# ccu_board.net
KiCad netlist of a schematic drawn in EAGLE
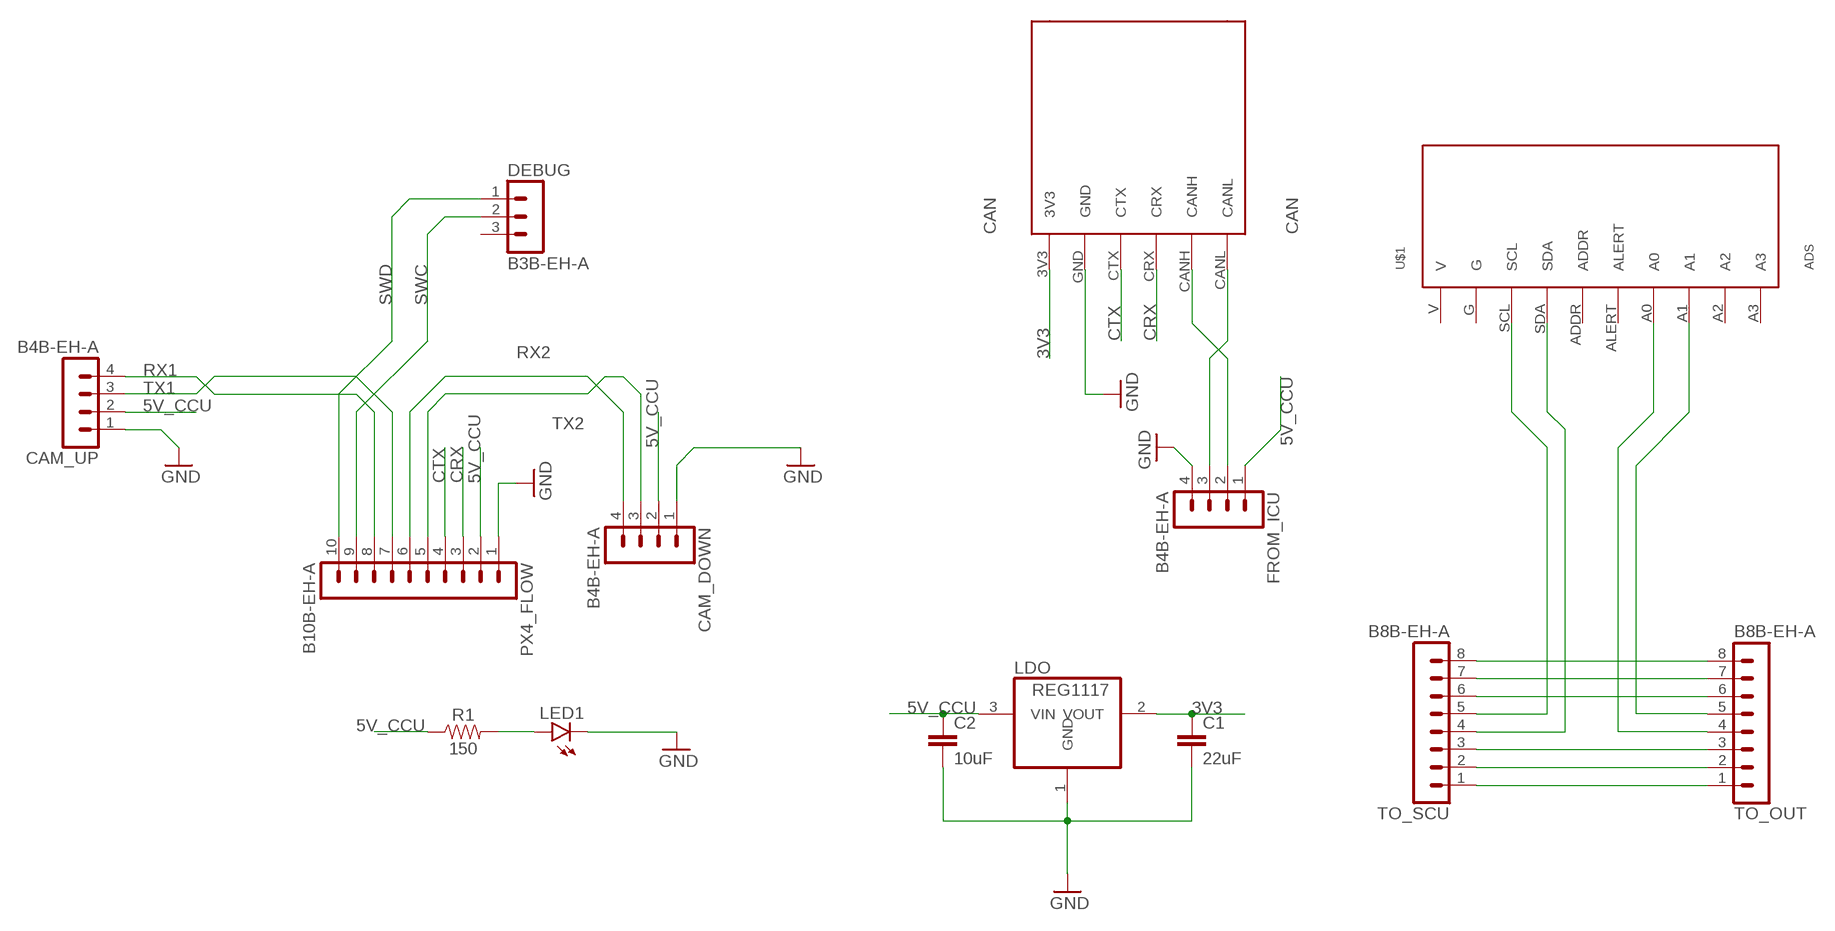
[diagram p0: schematic, sheet 1]

(export (version "E")
  (design (tool "Eeschema 10.0.6"))
  (components
    (comp (ref "C1")
      (value "22uF")
      (footprint "eagle-import:0805")
      (libsource (lib "eagle-import") (part "22UF-0805-6.3V-20%"))
    )
    (comp (ref "C2")
      (value "10uF")
      (footprint "eagle-import:0805")
      (libsource (lib "eagle-import") (part "22UF-0805-16V-20%"))
    )
    (comp (ref "CAM_DOWN")
      (value "B4B-EH-A")
      (footprint "eagle-import:B4B-EH-A")
      (libsource (lib "eagle-import") (part "B4B-EH-A"))
    )
    (comp (ref "CAM_UP")
      (value "B4B-EH-A")
      (footprint "eagle-import:B4B-EH-A")
      (libsource (lib "eagle-import") (part "B4B-EH-A"))
    )
    (comp (ref "CAN")
      (value "CAN")
      (footprint "eagle-import:CAN")
      (libsource (lib "eagle-import") (part "CAN"))
    )
    (comp (ref "DEBUG")
      (value "B3B-EH-A")
      (footprint "eagle-import:B3B-EH-A")
      (libsource (lib "eagle-import") (part "B3B-EH-A"))
    )
    (comp (ref "FROM_ICU")
      (value "B4B-EH-A")
      (footprint "eagle-import:B4B-EH-A")
      (libsource (lib "eagle-import") (part "B4B-EH-A"))
    )
    (comp (ref "LDO")
      (value "REG1117")
      (footprint "eagle-import:SOT223")
      (libsource (lib "eagle-import") (part "REG1117"))
    )
    (comp (ref "LED1")
      (value "LED5MM")
      (footprint "eagle-import:LED5MM")
      (libsource (lib "eagle-import") (part "LED5MM"))
    )
    (comp (ref "PX4_FLOW")
      (value "B10B-EH-A")
      (footprint "eagle-import:B10B-EH-A")
      (libsource (lib "eagle-import") (part "B10B-EH-A"))
    )
    (comp (ref "R1")
      (value "150")
      (footprint "eagle-import:AXIAL-0.3")
      (libsource (lib "eagle-import") (part "RESISTORAXIAL-0.3"))
    )
    (comp (ref "TO_OUT")
      (value "B8B-EH-A")
      (footprint "eagle-import:B8B-EH-A")
      (libsource (lib "eagle-import") (part "B8B-EH-A"))
    )
    (comp (ref "TO_SCU")
      (value "B8B-EH-A")
      (footprint "eagle-import:B8B-EH-A")
      (libsource (lib "eagle-import") (part "B8B-EH-A"))
    )
    (comp (ref "U$1")
      (value "ADS")
      (footprint "eagle-import:ADS")
      (libsource (lib "eagle-import") (part "ADS"))
    )
  )
  (nets
    (net (code "1") (name "/3V3") (class "Default")
      (node (ref "C1") (pin "1") (pinfunction "1_1") (pintype "passive"))
      (node (ref "CAN") (pin "3V3") (pinfunction "3V3_3V3") (pintype "bidirectional"))
      (node (ref "LDO") (pin "2") (pinfunction "VOUT_2") (pintype "output"))
    )
    (net (code "2") (name "/5V_CCU") (class "Default")
      (node (ref "C2") (pin "1") (pinfunction "1_1") (pintype "passive"))
      (node (ref "CAM_DOWN") (pin "2") (pinfunction "2_2") (pintype "passive"))
      (node (ref "CAM_UP") (pin "2") (pinfunction "2_2") (pintype "passive"))
      (node (ref "FROM_ICU") (pin "1") (pinfunction "1_1") (pintype "passive"))
      (node (ref "LDO") (pin "3") (pinfunction "VIN_3") (pintype "input"))
      (node (ref "PX4_FLOW") (pin "2") (pinfunction "2_2") (pintype "passive"))
      (node (ref "R1") (pin "P$1") (pinfunction "1_P$1") (pintype "passive"))
    )
    (net (code "3") (name "/CRX") (class "Default")
      (node (ref "CAN") (pin "CRX") (pinfunction "CRX_CRX") (pintype "bidirectional"))
      (node (ref "PX4_FLOW") (pin "3") (pinfunction "3_3") (pintype "passive"))
    )
    (net (code "4") (name "/CTX") (class "Default")
      (node (ref "CAN") (pin "CTX") (pinfunction "CTX_CTX") (pintype "bidirectional"))
      (node (ref "PX4_FLOW") (pin "4") (pinfunction "4_4") (pintype "passive"))
    )
    (net (code "5") (name "/RX1") (class "Default")
      (node (ref "CAM_UP") (pin "4") (pinfunction "4_4") (pintype "passive"))
      (node (ref "PX4_FLOW") (pin "8") (pinfunction "8_8") (pintype "passive"))
    )
    (net (code "6") (name "/RX2") (class "Default")
      (node (ref "CAM_DOWN") (pin "4") (pinfunction "4_4") (pintype "passive"))
      (node (ref "PX4_FLOW") (pin "6") (pinfunction "6_6") (pintype "passive"))
    )
    (net (code "7") (name "/SWC") (class "Default")
      (node (ref "DEBUG") (pin "2") (pinfunction "2_2") (pintype "passive"))
      (node (ref "PX4_FLOW") (pin "9") (pinfunction "9_9") (pintype "passive"))
    )
    (net (code "8") (name "/SWD") (class "Default")
      (node (ref "DEBUG") (pin "1") (pinfunction "1_1") (pintype "passive"))
      (node (ref "PX4_FLOW") (pin "10") (pinfunction "10_10") (pintype "passive"))
    )
    (net (code "9") (name "/TX1") (class "Default")
      (node (ref "CAM_UP") (pin "3") (pinfunction "3_3") (pintype "passive"))
      (node (ref "PX4_FLOW") (pin "7") (pinfunction "7_7") (pintype "passive"))
    )
    (net (code "10") (name "/TX2") (class "Default")
      (node (ref "CAM_DOWN") (pin "3") (pinfunction "3_3") (pintype "passive"))
      (node (ref "PX4_FLOW") (pin "5") (pinfunction "5_5") (pintype "passive"))
    )
    (net (code "11") (name "GND") (class "Default")
      (node (ref "C1") (pin "2") (pinfunction "2_2") (pintype "passive"))
      (node (ref "C2") (pin "2") (pinfunction "2_2") (pintype "passive"))
      (node (ref "CAM_DOWN") (pin "1") (pinfunction "1_1") (pintype "passive"))
      (node (ref "CAM_UP") (pin "1") (pinfunction "1_1") (pintype "passive"))
      (node (ref "CAN") (pin "GND") (pinfunction "GND_GND") (pintype "bidirectional"))
      (node (ref "FROM_ICU") (pin "4") (pinfunction "4_4") (pintype "passive"))
      (node (ref "LDO") (pin "1") (pinfunction "GND_1") (pintype "power_in"))
      (node (ref "LED1") (pin "K") (pinfunction "C_K") (pintype "passive"))
      (node (ref "PX4_FLOW") (pin "1") (pinfunction "1_1") (pintype "passive"))
    )
    (net (code "12") (name "Net-(CAN-PadCANH)") (class "Default")
      (node (ref "CAN") (pin "CANH") (pinfunction "CANH_CANH") (pintype "bidirectional"))
      (node (ref "FROM_ICU") (pin "2") (pinfunction "2_2") (pintype "passive"))
    )
    (net (code "13") (name "Net-(CAN-PadCANL)") (class "Default")
      (node (ref "CAN") (pin "CANL") (pinfunction "CANL_CANL") (pintype "bidirectional"))
      (node (ref "FROM_ICU") (pin "3") (pinfunction "3_3") (pintype "passive"))
    )
    (net (code "14") (name "Net-(R1-2)") (class "Default")
      (node (ref "LED1") (pin "A") (pinfunction "A_A") (pintype "passive"))
      (node (ref "R1") (pin "P$2") (pinfunction "2_P$2") (pintype "passive"))
    )
    (net (code "15") (name "Net-(TO_OUT-Pad1)") (class "Default")
      (node (ref "TO_OUT") (pin "1") (pinfunction "1_1") (pintype "passive"))
      (node (ref "TO_SCU") (pin "1") (pinfunction "1_1") (pintype "passive"))
    )
    (net (code "16") (name "Net-(TO_OUT-Pad2)") (class "Default")
      (node (ref "TO_OUT") (pin "2") (pinfunction "2_2") (pintype "passive"))
      (node (ref "TO_SCU") (pin "2") (pinfunction "2_2") (pintype "passive"))
    )
    (net (code "17") (name "Net-(TO_OUT-Pad3)") (class "Default")
      (node (ref "TO_OUT") (pin "3") (pinfunction "3_3") (pintype "passive"))
      (node (ref "TO_SCU") (pin "3") (pinfunction "3_3") (pintype "passive"))
    )
    (net (code "18") (name "Net-(TO_OUT-Pad4)") (class "Default")
      (node (ref "TO_OUT") (pin "4") (pinfunction "4_4") (pintype "passive"))
      (node (ref "U$1") (pin "A0") (pinfunction "A0_A0") (pintype "bidirectional"))
    )
    (net (code "19") (name "Net-(TO_OUT-Pad5)") (class "Default")
      (node (ref "TO_OUT") (pin "5") (pinfunction "5_5") (pintype "passive"))
      (node (ref "U$1") (pin "A1") (pinfunction "A1_A1") (pintype "bidirectional"))
    )
    (net (code "20") (name "Net-(TO_OUT-Pad6)") (class "Default")
      (node (ref "TO_OUT") (pin "6") (pinfunction "6_6") (pintype "passive"))
      (node (ref "TO_SCU") (pin "6") (pinfunction "6_6") (pintype "passive"))
    )
    (net (code "21") (name "Net-(TO_OUT-Pad7)") (class "Default")
      (node (ref "TO_OUT") (pin "7") (pinfunction "7_7") (pintype "passive"))
      (node (ref "TO_SCU") (pin "7") (pinfunction "7_7") (pintype "passive"))
    )
    (net (code "22") (name "Net-(TO_OUT-Pad8)") (class "Default")
      (node (ref "TO_OUT") (pin "8") (pinfunction "8_8") (pintype "passive"))
      (node (ref "TO_SCU") (pin "8") (pinfunction "8_8") (pintype "passive"))
    )
    (net (code "23") (name "Net-(TO_SCU-Pad4)") (class "Default")
      (node (ref "TO_SCU") (pin "4") (pinfunction "4_4") (pintype "passive"))
      (node (ref "U$1") (pin "SDA") (pinfunction "SDA_SDA") (pintype "bidirectional"))
    )
    (net (code "24") (name "Net-(TO_SCU-Pad5)") (class "Default")
      (node (ref "TO_SCU") (pin "5") (pinfunction "5_5") (pintype "passive"))
      (node (ref "U$1") (pin "SCL") (pinfunction "SCL_SCL") (pintype "bidirectional"))
    )
    (net (code "25") (name "unconnected-(DEBUG-Pad3)") (class "Default")
      (node (ref "DEBUG") (pin "3") (pinfunction "3_3") (pintype "passive"))
    )
    (net (code "26") (name "unconnected-(U$1-PadA2)") (class "Default")
      (node (ref "U$1") (pin "A2") (pinfunction "A2_A2") (pintype "bidirectional"))
    )
    (net (code "27") (name "unconnected-(U$1-PadA3)") (class "Default")
      (node (ref "U$1") (pin "A3") (pinfunction "A3_A3") (pintype "bidirectional"))
    )
    (net (code "28") (name "unconnected-(U$1-PadADDR)") (class "Default")
      (node (ref "U$1") (pin "ADDR") (pinfunction "ADDR_ADDR") (pintype "bidirectional"))
    )
    (net (code "29") (name "unconnected-(U$1-PadALERT)") (class "Default")
      (node (ref "U$1") (pin "ALERT") (pinfunction "ALERT_ALERT") (pintype "bidirectional"))
    )
    (net (code "30") (name "unconnected-(U$1-PadG)") (class "Default")
      (node (ref "U$1") (pin "G") (pinfunction "G_G") (pintype "bidirectional"))
    )
    (net (code "31") (name "unconnected-(U$1-PadV)") (class "Default")
      (node (ref "U$1") (pin "V") (pinfunction "V_V") (pintype "bidirectional"))
    )
  )
)
